# Oscillator.net
KiCad netlist of a schematic drawn in Altium Designer
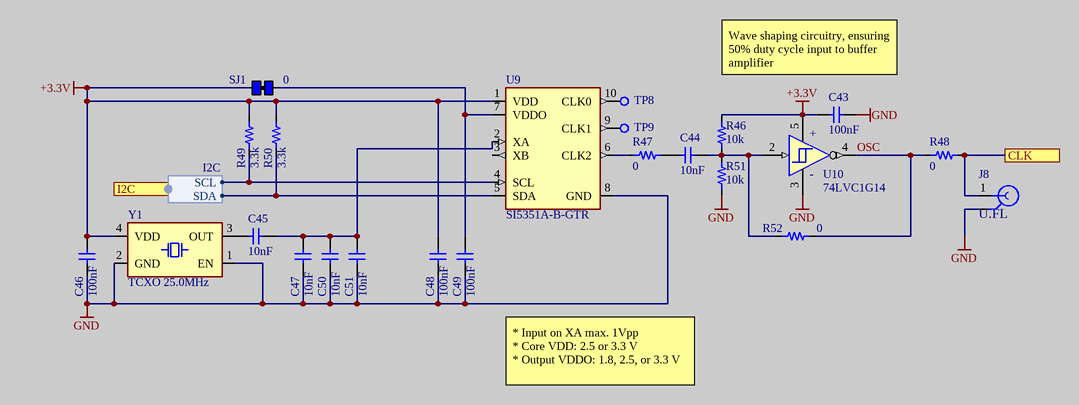
[diagram p0: Oscillator.SchDoc]

(export (version "E")
  (design (tool "Eeschema 10.0.6"))
  (components
    (comp (ref "C43")
      (value "100nF")
      (footprint "0603-C-N")
      (description "WCAP-CSGP Multilayer Ceramic Chip Capacitor, General Purpose, size 0603, X7R, 100nF, 50VDC")
      (fields (field (name "TOLERANCE") "10%") (field (name "JLCPCB PART #") "C14663"))
      (libsource (lib "7c7 Engineering") (part "CAP-NP-2"))
    )
    (comp (ref "C44")
      (value "10nF")
      (footprint "0603-C-N")
      (description "Multilayer Ceramic Capacitor, Grm Series, 0.01 F, 5%, C0g / Np0, 50 V, 0603 [1608 Metric]")
      (fields (field (name "VOLTAGE") "50V") (field (name "TOLERANCE") "5%"))
      (libsource (lib "7c7 Engineering") (part "CAP-NP-2"))
    )
    (comp (ref "C45")
      (value "10nF")
      (footprint "0603-C-N")
      (description "Multilayer Ceramic Capacitor, Grm Series, 0.01 F, 5%, C0g / Np0, 50 V, 0603 [1608 Metric]")
      (fields (field (name "VOLTAGE") "50V") (field (name "TOLERANCE") "5%"))
      (libsource (lib "7c7 Engineering") (part "CAP-NP-2"))
    )
    (comp (ref "C46")
      (value "100nF")
      (footprint "0603-C-N")
      (description "WCAP-CSGP Multilayer Ceramic Chip Capacitor, General Purpose, size 0603, X7R, 100nF, 50VDC")
      (fields (field (name "TOLERANCE") "10%") (field (name "JLCPCB PART #") "C14663"))
      (libsource (lib "7c7 Engineering") (part "CAP-NP-2"))
    )
    (comp (ref "C47")
      (value "10nF")
      (footprint "0603-C-N")
      (description "Multilayer Ceramic Capacitor, Grm Series, 0.01 F, 5%, C0g / Np0, 50 V, 0603 [1608 Metric]")
      (fields (field (name "VOLTAGE") "50V") (field (name "TOLERANCE") "5%"))
      (libsource (lib "7c7 Engineering") (part "CAP-NP-2"))
    )
    (comp (ref "C48")
      (value "100nF")
      (footprint "0603-C-N")
      (description "WCAP-CSGP Multilayer Ceramic Chip Capacitor, General Purpose, size 0603, X7R, 100nF, 50VDC")
      (fields (field (name "TOLERANCE") "10%") (field (name "JLCPCB PART #") "C14663"))
      (libsource (lib "7c7 Engineering") (part "CAP-NP-2"))
    )
    (comp (ref "C49")
      (value "100nF")
      (footprint "0603-C-N")
      (description "WCAP-CSGP Multilayer Ceramic Chip Capacitor, General Purpose, size 0603, X7R, 100nF, 50VDC")
      (fields (field (name "TOLERANCE") "10%") (field (name "JLCPCB PART #") "C14663"))
      (libsource (lib "7c7 Engineering") (part "CAP-NP-2"))
    )
    (comp (ref "C50")
      (value "10nF")
      (footprint "0603-C-N")
      (description "Multilayer Ceramic Capacitor, Grm Series, 0.01 F, 5%, C0g / Np0, 50 V, 0603 [1608 Metric]")
      (fields (field (name "VOLTAGE") "50V") (field (name "TOLERANCE") "5%"))
      (libsource (lib "7c7 Engineering") (part "CAP-NP-2"))
    )
    (comp (ref "C51")
      (value "10nF")
      (footprint "0603-C-N")
      (description "Multilayer Ceramic Capacitor, Grm Series, 0.01 F, 5%, C0g / Np0, 50 V, 0603 [1608 Metric]")
      (fields (field (name "VOLTAGE") "50V") (field (name "TOLERANCE") "5%"))
      (libsource (lib "7c7 Engineering") (part "CAP-NP-2"))
    )
    (comp (ref "J8")
      (value "U.FL-R-SMT(10)")
      (footprint "HRS-U.FL-R-SMT_V")
      (fields (field (name "JLCPCB PART #") "C88373") (field (name "MANUFACTURER") "Hirose Electric"))
      (libsource (lib "7c7 Engineering") (part "CN_COAX"))
    )
    (comp (ref "R46")
      (value "10k")
      (footprint "0603-R-N")
      (description "Chip Resistor, Thick Film, General Purpose, 0603, 100mW, 50V, 10 kOhm, +/-1%")
      (fields (field (name "TOLERANCE") "1%") (field (name "JLCPCB PART #") "C25804"))
      (libsource (lib "7c7 Engineering") (part "RES"))
    )
    (comp (ref "R47")
      (value "0")
      (footprint "0603-R-N")
      (description "Chip Jumper, Thick Film, Jumper, 0603, 100mW, 1A, 0 Ohm, <50 mOhm")
      (fields (field (name "FLIR PART #") "YRES0E-1") (field (name "TOLERANCE") "50 mOhm"))
      (libsource (lib "7c7 Engineering") (part "RES"))
    )
    (comp (ref "R48")
      (value "0")
      (footprint "0603-R-N")
      (description "Chip Jumper, Thick Film, Jumper, 0603, 100mW, 1A, 0 Ohm, <50 mOhm")
      (fields (field (name "FLIR PART #") "YRES0E-1") (field (name "TOLERANCE") "50 mOhm"))
      (libsource (lib "7c7 Engineering") (part "RES"))
    )
    (comp (ref "R49")
      (value "3.3k")
      (footprint "0603-R-N")
      (description "Chip Resistor, Thick Film, General Purpose, 0603, 100mW, 50V, 3.3 kOhm, +/-1%")
      (fields (field (name "TOLERANCE") "1%") (field (name "JLCPCB PART #") "C22978"))
      (libsource (lib "7c7 Engineering") (part "RES"))
    )
    (comp (ref "R50")
      (value "3.3k")
      (footprint "0603-R-N")
      (description "Chip Resistor, Thick Film, General Purpose, 0603, 100mW, 50V, 3.3 kOhm, +/-1%")
      (fields (field (name "TOLERANCE") "1%") (field (name "JLCPCB PART #") "C22978"))
      (libsource (lib "7c7 Engineering") (part "RES"))
    )
    (comp (ref "R51")
      (value "10k")
      (footprint "0603-R-N")
      (description "Chip Resistor, Thick Film, General Purpose, 0603, 100mW, 50V, 10 kOhm, +/-1%")
      (fields (field (name "TOLERANCE") "1%") (field (name "JLCPCB PART #") "C25804"))
      (libsource (lib "7c7 Engineering") (part "RES"))
    )
    (comp (ref "R52")
      (value "0")
      (footprint "0603-R-N")
      (description "Chip Jumper, Thick Film, Jumper, 0603, 100mW, 1A, 0 Ohm, <50 mOhm")
      (fields (field (name "FLIR PART #") "YRES0E-1") (field (name "TOLERANCE") "50 mOhm"))
      (libsource (lib "7c7 Engineering") (part "RES"))
    )
    (comp (ref "SJ1")
      (value "0")
      (footprint "SJ_0603_1A")
      (description "Solder Jumper, Thick Film, Jumper, 0603, 100mW, 1A, 0 Ohm, <50 mOhm")
      (fields (field (name "JLCPCB PART #") "C876125") (field (name "TOLERANCE") "50 mOhm"))
      (libsource (lib "7c7 Engineering") (part "SJ-C"))
    )
    (comp (ref "TP8")
      (value "Testpad with multiple sizes")
      (footprint "TP_1.5mm")
      (description "Testpad land")
      (libsource (lib "7c7 Engineering") (part "Testpad"))
    )
    (comp (ref "TP9")
      (value "Testpad with multiple sizes")
      (footprint "TP_1.5mm")
      (description "Testpad land")
      (libsource (lib "7c7 Engineering") (part "Testpad"))
    )
    (comp (ref "U9")
      (value "SI5351A-B-GTR")
      (footprint "VSSOP10-N")
      (description "IC CLK GENERATOR 160MHZ 10MSOP")
      (fields (field (name "JLCPCB PART #") "C504891"))
      (libsource (lib "7c7 Engineering") (part "IC_SI5351A"))
    )
    (comp (ref "U10")
      (value "74LVC1G14")
      (footprint "SOT25-N")
      (description "Single 1.65-V to 5.5-V inverter with Schmitt-Trigger inputs 5-SOT-23 -40 to 125")
      (fields (field (name "JLCPCB PART #") "C7835") (field (name "Comment") "SN74LVC1G14DBVR"))
      (libsource (lib "7c7 Engineering") (part "IC_INVERTER"))
    )
    (comp (ref "Y1")
      (value "TCXO 25.0MHz")
      (footprint "WE-SPXO_IQXO-791")
      (description "TCXO 25MHz, 3.3V")
      (fields (field (name "JLCPCB PART #") "C5180005") (field (name "Comment") "SX2T25.000B010J020S"))
      (libsource (lib "7c7 Engineering") (part "IC_OSCILLATOR"))
    )
  )
  (nets
    (net (code "2") (name "+3.3V") (class "Default")
      (node (ref "C43") (pin "2") (pinfunction "2_2") (pintype "passive"))
      (node (ref "C46") (pin "1") (pinfunction "1_1") (pintype "passive"))
      (node (ref "C48") (pin "1") (pinfunction "1_1") (pintype "passive"))
      (node (ref "R46") (pin "1") (pinfunction "1_1") (pintype "passive"))
      (node (ref "R49") (pin "2") (pinfunction "2_2") (pintype "passive"))
      (node (ref "R50") (pin "2") (pinfunction "2_2") (pintype "passive"))
      (node (ref "SJ1") (pin "1") (pinfunction "L_1") (pintype "passive"))
      (node (ref "U10") (pin "5") (pinfunction "VCC_5") (pintype "power_in"))
      (node (ref "U9") (pin "1") (pinfunction "VDD_1") (pintype "power_in"))
      (node (ref "Y1") (pin "4") (pinfunction "VDD_4") (pintype "passive"))
    )
    (net (code "3") (name "/CLK") (class "Default")
      (node (ref "J8") (pin "1") (pinfunction "SIG_1") (pintype "passive"))
      (node (ref "R48") (pin "1") (pinfunction "1_1") (pintype "passive"))
    )
    (net (code "4") (name "/OSC") (class "Default")
      (node (ref "R48") (pin "2") (pinfunction "2_2") (pintype "passive"))
      (node (ref "R52") (pin "2") (pinfunction "2_2") (pintype "passive"))
      (node (ref "U10") (pin "4") (pinfunction "Y_4") (pintype "output"))
    )
    (net (code "6") (name "GND") (class "Default")
      (node (ref "C43") (pin "1") (pinfunction "1_1") (pintype "passive"))
      (node (ref "C46") (pin "2") (pinfunction "2_2") (pintype "passive"))
      (node (ref "C47") (pin "1") (pinfunction "1_1") (pintype "passive"))
      (node (ref "C48") (pin "2") (pinfunction "2_2") (pintype "passive"))
      (node (ref "C49") (pin "2") (pinfunction "2_2") (pintype "passive"))
      (node (ref "C50") (pin "1") (pinfunction "1_1") (pintype "passive"))
      (node (ref "C51") (pin "1") (pinfunction "1_1") (pintype "passive"))
      (node (ref "J8") (pin "2") (pinfunction "GND_2") (pintype "passive"))
      (node (ref "R51") (pin "2") (pinfunction "2_2") (pintype "passive"))
      (node (ref "U10") (pin "3") (pinfunction "GND_3") (pintype "power_in"))
      (node (ref "U9") (pin "8") (pinfunction "GND_8") (pintype "power_in"))
      (node (ref "Y1") (pin "1") (pinfunction "EN_1") (pintype "passive"))
      (node (ref "Y1") (pin "2") (pinfunction "GND_2") (pintype "passive"))
    )
    (net (code "7") (name "Net-(C44-Pad1)") (class "Default")
      (node (ref "C44") (pin "1") (pinfunction "1_1") (pintype "passive"))
      (node (ref "R47") (pin "1") (pinfunction "1_1") (pintype "passive"))
    )
    (net (code "8") (name "Net-(SJ1-R)") (class "Default")
      (node (ref "C49") (pin "1") (pinfunction "1_1") (pintype "passive"))
      (node (ref "SJ1") (pin "2") (pinfunction "R_2") (pintype "passive"))
      (node (ref "U9") (pin "7") (pinfunction "VDDO_7") (pintype "power_in"))
    )
    (net (code "9") (name "Net-(U9-CLK0)") (class "Default")
      (node (ref "TP8") (pin "1") (pinfunction "Pad_1") (pintype "passive"))
      (node (ref "U9") (pin "10") (pinfunction "CLK0_10") (pintype "output"))
    )
    (net (code "10") (name "Net-(U9-CLK1)") (class "Default")
      (node (ref "TP9") (pin "1") (pinfunction "Pad_1") (pintype "passive"))
      (node (ref "U9") (pin "9") (pinfunction "CLK1_9") (pintype "output"))
    )
    (net (code "11") (name "Net-(U9-CLK2)") (class "Default")
      (node (ref "R47") (pin "2") (pinfunction "2_2") (pintype "passive"))
      (node (ref "U9") (pin "6") (pinfunction "CLK2_6") (pintype "output"))
    )
    (net (code "12") (name "Net-(U9-SCL)") (class "Default")
      (node (ref "R49") (pin "1") (pinfunction "1_1") (pintype "passive"))
      (node (ref "U9") (pin "4") (pinfunction "SCL_4") (pintype "input"))
    )
    (net (code "13") (name "Net-(U9-SDA)") (class "Default")
      (node (ref "R50") (pin "1") (pinfunction "1_1") (pintype "passive"))
      (node (ref "U9") (pin "5") (pinfunction "SDA_5") (pintype "bidirectional"))
    )
    (net (code "14") (name "Net-(U9-XA)") (class "Default")
      (node (ref "C45") (pin "2") (pinfunction "2_2") (pintype "passive"))
      (node (ref "C47") (pin "2") (pinfunction "2_2") (pintype "passive"))
      (node (ref "C50") (pin "2") (pinfunction "2_2") (pintype "passive"))
      (node (ref "C51") (pin "2") (pinfunction "2_2") (pintype "passive"))
      (node (ref "U9") (pin "2") (pinfunction "XA_2") (pintype "input"))
    )
    (net (code "15") (name "Net-(U10-A)") (class "Default")
      (node (ref "C44") (pin "2") (pinfunction "2_2") (pintype "passive"))
      (node (ref "R46") (pin "2") (pinfunction "2_2") (pintype "passive"))
      (node (ref "R51") (pin "1") (pinfunction "1_1") (pintype "passive"))
      (node (ref "R52") (pin "1") (pinfunction "1_1") (pintype "passive"))
      (node (ref "U10") (pin "2") (pinfunction "A_2") (pintype "input"))
    )
    (net (code "16") (name "Net-(Y1-OUT)") (class "Default")
      (node (ref "C45") (pin "1") (pinfunction "1_1") (pintype "passive"))
      (node (ref "Y1") (pin "3") (pinfunction "OUT_3") (pintype "passive"))
    )
    (net (code "17") (name "unconnected-(U9-XB-Pad3)") (class "Default")
      (node (ref "U9") (pin "3") (pinfunction "XB_3") (pintype "output"))
    )
  )
)
